# DualMax485.net
KiCad netlist of a schematic drawn in EAGLE
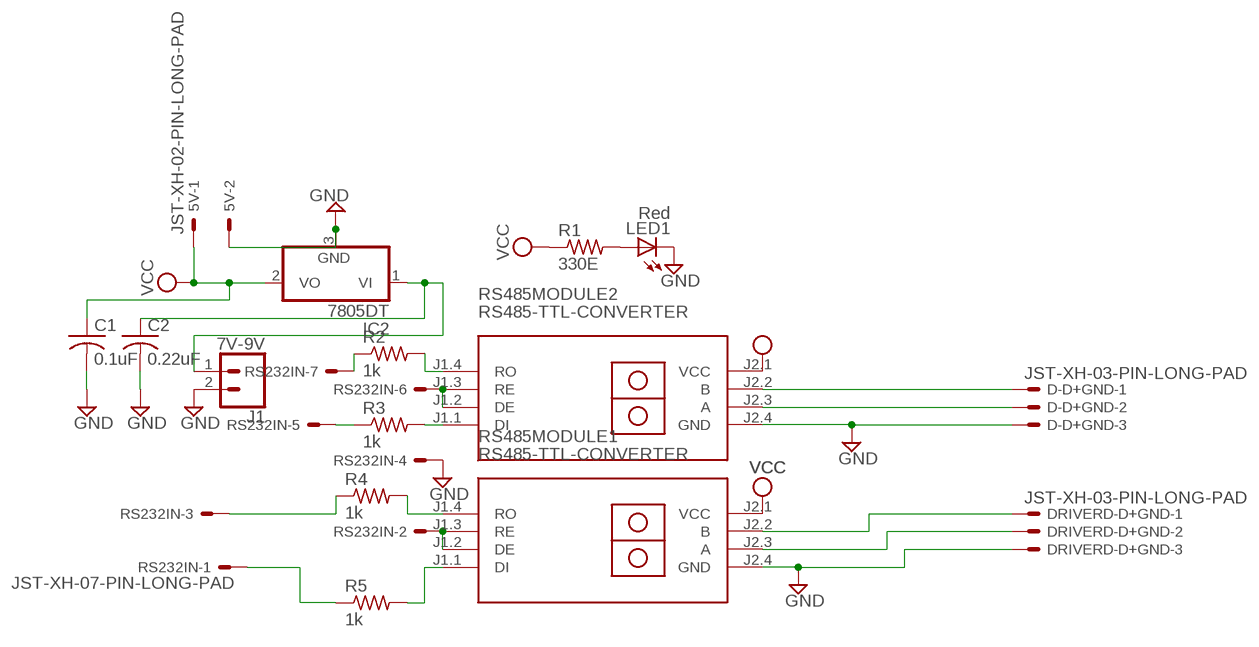
[diagram p0: schematic, sheet 1]

(export (version "E")
  (design (tool "Eeschema 10.0.6"))
  (components
    (comp (ref "5V")
      (value "JST-XH-02-PIN-LONG-PAD")
      (footprint "eagle-import:JST-XH-02-PACKAGE-LONG-PAD")
      (libsource (lib "eagle-import") (part "JST-XH-02-PIN-LONG-PAD"))
    )
    (comp (ref "C1")
      (value "0.1uF")
      (footprint "eagle-import:C0805")
      (libsource (lib "eagle-import") (part "C-USC0805"))
    )
    (comp (ref "C2")
      (value "0.22uF")
      (footprint "eagle-import:C0805")
      (libsource (lib "eagle-import") (part "C-USC0805"))
    )
    (comp (ref "D-D+GND")
      (value "JST-XH-03-PIN-LONG-PAD")
      (footprint "eagle-import:JST-XH-03-PACKAGE-LONG-PAD")
      (libsource (lib "eagle-import") (part "JST-XH-03-PIN-LONG-PAD"))
    )
    (comp (ref "DRIVERD-D+GND")
      (value "JST-XH-03-PIN-LONG-PAD")
      (footprint "eagle-import:JST-XH-03-PACKAGE-LONG-PAD")
      (libsource (lib "eagle-import") (part "JST-XH-03-PIN-LONG-PAD"))
    )
    (comp (ref "IC2")
      (value "7805DT")
      (footprint "eagle-import:TO252")
      (libsource (lib "eagle-import") (part "78DT05"))
    )
    (comp (ref "J1")
      (value "7V-9V")
      (footprint "eagle-import:SCREWTERMINAL-5MM-2")
      (libsource (lib "eagle-import") (part "CONN_025MM"))
    )
    (comp (ref "LED1")
      (value "Red")
      (footprint "eagle-import:CHIPLED_0805")
      (libsource (lib "eagle-import") (part "LEDCHIPLED_0805"))
    )
    (comp (ref "R1")
      (value "330E")
      (footprint "eagle-import:M0805")
      (libsource (lib "eagle-import") (part "R-US_M0805"))
    )
    (comp (ref "R2")
      (value "1k")
      (footprint "eagle-import:M0805")
      (libsource (lib "eagle-import") (part "R-US_M0805"))
    )
    (comp (ref "R3")
      (value "1k")
      (footprint "eagle-import:M0805")
      (libsource (lib "eagle-import") (part "R-US_M0805"))
    )
    (comp (ref "R4")
      (value "1k")
      (footprint "eagle-import:M0805")
      (libsource (lib "eagle-import") (part "R-US_M0805"))
    )
    (comp (ref "R5")
      (value "1k")
      (footprint "eagle-import:M0805")
      (libsource (lib "eagle-import") (part "R-US_M0805"))
    )
    (comp (ref "RS232IN")
      (value "JST-XH-07-PIN-LONG-PAD")
      (footprint "eagle-import:JST-XH-07-PACKAGE-LONG-PAD")
      (libsource (lib "eagle-import") (part "JST-XH-07-PIN-LONG-PAD"))
    )
    (comp (ref "RS485MODULE1")
      (value "RS485-TTL-CONVERTER")
      (footprint "eagle-import:RS485-TTL-CONVERTER")
      (libsource (lib "eagle-import") (part "RS485-TTL-CONVERTER"))
    )
    (comp (ref "RS485MODULE2")
      (value "RS485-TTL-CONVERTER")
      (footprint "eagle-import:RS485-TTL-CONVERTER")
      (libsource (lib "eagle-import") (part "RS485-TTL-CONVERTER"))
    )
  )
  (nets
    (net (code "1") (name "GND") (class "Default")
      (node (ref "5V") (pin "2") (pinfunction "S_2") (pintype "passive"))
      (node (ref "C1") (pin "2") (pinfunction "2_2") (pintype "passive"))
      (node (ref "C2") (pin "2") (pinfunction "2_2") (pintype "passive"))
      (node (ref "D-D+GND") (pin "3") (pinfunction "S_3") (pintype "passive"))
      (node (ref "DRIVERD-D+GND") (pin "3") (pinfunction "S_3") (pintype "passive"))
      (node (ref "IC2") (pin "3") (pinfunction "GND_3") (pintype "passive"))
      (node (ref "J1") (pin "2") (pinfunction "2_2") (pintype "passive"))
      (node (ref "LED1") (pin "C") (pinfunction "C_C") (pintype "passive"))
      (node (ref "RS232IN") (pin "4") (pinfunction "S_4") (pintype "passive"))
      (node (ref "RS485MODULE1") (pin "J2.4") (pinfunction "GND_J2.4") (pintype "power_in"))
      (node (ref "RS485MODULE2") (pin "J2.4") (pinfunction "GND_J2.4") (pintype "power_in"))
    )
    (net (code "2") (name "Net-(D-D+GNDA-S)") (class "Default")
      (node (ref "D-D+GND") (pin "1") (pinfunction "S_1") (pintype "passive"))
      (node (ref "RS485MODULE2") (pin "J2.2") (pinfunction "B_J2.2") (pintype "passive"))
    )
    (net (code "3") (name "Net-(D-D+GNDB-S)") (class "Default")
      (node (ref "D-D+GND") (pin "2") (pinfunction "S_2") (pintype "passive"))
      (node (ref "RS485MODULE2") (pin "J2.3") (pinfunction "A_J2.3") (pintype "passive"))
    )
    (net (code "4") (name "Net-(DRIVERD-D+GNDA-S)") (class "Default")
      (node (ref "DRIVERD-D+GND") (pin "1") (pinfunction "S_1") (pintype "passive"))
      (node (ref "RS485MODULE1") (pin "J2.2") (pinfunction "B_J2.2") (pintype "passive"))
    )
    (net (code "5") (name "Net-(DRIVERD-D+GNDB-S)") (class "Default")
      (node (ref "DRIVERD-D+GND") (pin "2") (pinfunction "S_2") (pintype "passive"))
      (node (ref "RS485MODULE1") (pin "J2.3") (pinfunction "A_J2.3") (pintype "passive"))
    )
    (net (code "6") (name "Net-(IC2-VI)") (class "Default")
      (node (ref "C2") (pin "1") (pinfunction "1_1") (pintype "passive"))
      (node (ref "IC2") (pin "1") (pinfunction "VI_1") (pintype "input"))
      (node (ref "J1") (pin "1") (pinfunction "1_1") (pintype "passive"))
    )
    (net (code "7") (name "Net-(LED1-PadA)") (class "Default")
      (node (ref "LED1") (pin "A") (pinfunction "A_A") (pintype "passive"))
      (node (ref "R1") (pin "2") (pinfunction "2_2") (pintype "passive"))
    )
    (net (code "8") (name "Net-(RS232INA-S)") (class "Default")
      (node (ref "R5") (pin "1") (pinfunction "1_1") (pintype "passive"))
      (node (ref "RS232IN") (pin "1") (pinfunction "S_1") (pintype "passive"))
    )
    (net (code "9") (name "Net-(RS232INB-S)") (class "Default")
      (node (ref "RS232IN") (pin "2") (pinfunction "S_2") (pintype "passive"))
      (node (ref "RS485MODULE1") (pin "J1.2") (pinfunction "DE_J1.2") (pintype "passive"))
      (node (ref "RS485MODULE1") (pin "J1.3") (pinfunction "RE_J1.3") (pintype "passive"))
    )
    (net (code "10") (name "Net-(RS232INC-S)") (class "Default")
      (node (ref "R4") (pin "1") (pinfunction "1_1") (pintype "passive"))
      (node (ref "RS232IN") (pin "3") (pinfunction "S_3") (pintype "passive"))
    )
    (net (code "11") (name "Net-(RS232INE-S)") (class "Default")
      (node (ref "R3") (pin "1") (pinfunction "1_1") (pintype "passive"))
      (node (ref "RS232IN") (pin "5") (pinfunction "S_5") (pintype "passive"))
    )
    (net (code "12") (name "Net-(RS232INF-S)") (class "Default")
      (node (ref "RS232IN") (pin "6") (pinfunction "S_6") (pintype "passive"))
      (node (ref "RS485MODULE2") (pin "J1.2") (pinfunction "DE_J1.2") (pintype "passive"))
      (node (ref "RS485MODULE2") (pin "J1.3") (pinfunction "RE_J1.3") (pintype "passive"))
    )
    (net (code "13") (name "Net-(RS232ING-S)") (class "Default")
      (node (ref "R2") (pin "1") (pinfunction "1_1") (pintype "passive"))
      (node (ref "RS232IN") (pin "7") (pinfunction "S_7") (pintype "passive"))
    )
    (net (code "14") (name "Net-(RS485MODULE1-DI)") (class "Default")
      (node (ref "R5") (pin "2") (pinfunction "2_2") (pintype "passive"))
      (node (ref "RS485MODULE1") (pin "J1.1") (pinfunction "DI_J1.1") (pintype "passive"))
    )
    (net (code "15") (name "Net-(RS485MODULE1-RO)") (class "Default")
      (node (ref "R4") (pin "2") (pinfunction "2_2") (pintype "passive"))
      (node (ref "RS485MODULE1") (pin "J1.4") (pinfunction "RO_J1.4") (pintype "passive"))
    )
    (net (code "16") (name "Net-(RS485MODULE2-DI)") (class "Default")
      (node (ref "R3") (pin "2") (pinfunction "2_2") (pintype "passive"))
      (node (ref "RS485MODULE2") (pin "J1.1") (pinfunction "DI_J1.1") (pintype "passive"))
    )
    (net (code "17") (name "Net-(RS485MODULE2-RO)") (class "Default")
      (node (ref "R2") (pin "2") (pinfunction "2_2") (pintype "passive"))
      (node (ref "RS485MODULE2") (pin "J1.4") (pinfunction "RO_J1.4") (pintype "passive"))
    )
    (net (code "18") (name "VCC") (class "Default")
      (node (ref "5V") (pin "1") (pinfunction "S_1") (pintype "passive"))
      (node (ref "C1") (pin "1") (pinfunction "1_1") (pintype "passive"))
      (node (ref "IC2") (pin "2") (pinfunction "VO_2") (pintype "passive"))
      (node (ref "R1") (pin "1") (pinfunction "1_1") (pintype "passive"))
      (node (ref "RS485MODULE1") (pin "J2.1") (pinfunction "VCC_J2.1") (pintype "power_in"))
      (node (ref "RS485MODULE2") (pin "J2.1") (pinfunction "VCC_J2.1") (pintype "power_in"))
    )
  )
)
